# LED_Schematic.net
KiCad netlist of a schematic drawn in Altium Designer
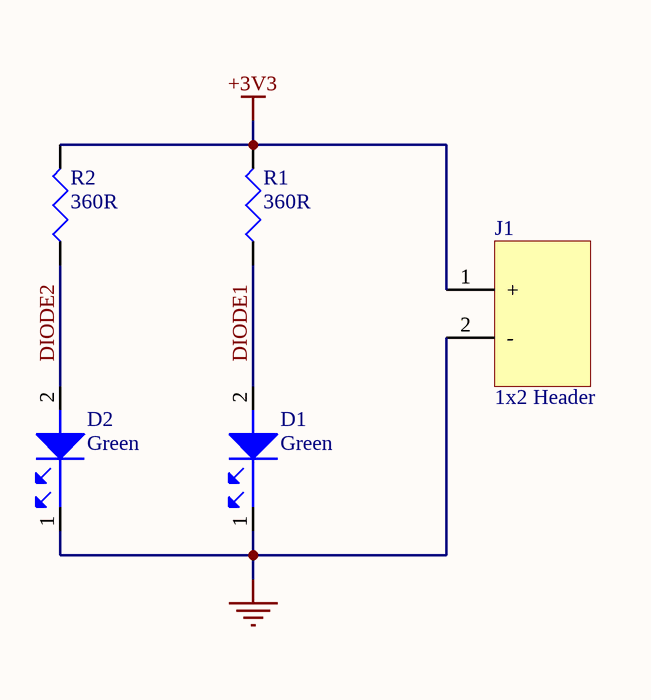
[diagram p0: LED Schematic.SchDoc]

(export (version "E")
  (design (tool "Eeschema 10.0.6"))
  (components
    (comp (ref "D1")
      (value "Green")
      (footprint "LED1540G")
      (description "Led Green/orange TSS-2 Type SMD")
      (fields
        (field (name "MANUFACTURER") "Panasonic")
        (field (name "MANUFACTURER PART NUMBER") "LNJ115W8ARA")
      )
      (libsource (lib "LED Schematic Library") (part "LNJ115W8ARA"))
    )
    (comp (ref "D2")
      (value "Green")
      (footprint "LED1540G")
      (description "Led Green/orange TSS-2 Type SMD")
      (fields
        (field (name "MANUFACTURER") "Panasonic")
        (field (name "MANUFACTURER PART NUMBER") "LNJ115W8ARA")
      )
      (libsource (lib "LED Schematic Library") (part "LNJ115W8ARA"))
    )
    (comp (ref "J1")
      (value "1x2 Header")
      (footprint "HDR1X2")
      (description "KK 254 Wire-to-Board Header, Vertical, with Friction Lock, 2 Circuits, Gold (Au) Plating")
      (fields (field (name "MANUFACTURER") "Molex") (field (name "MANUFACTURER PART NUMBER") "0022292021"))
      (libsource (lib "LED Schematic Library") (part "0022292021"))
    )
    (comp (ref "R1")
      (value "360R")
      (footprint "R0805")
      (description "SMD Chip Resistor, 360 Ohm, ± 1%, 125 mW, 0805 [2012 Metric], Thick Film, General Purpose")
      (fields
        (field (name "MANUFACTURER") "Vishay")
        (field (name "MANUFACTURER PART NUMBER") "CRCW0805360RFKEA")
      )
      (libsource (lib "LED Schematic Library") (part "CRCW0805360RFKEA"))
    )
    (comp (ref "R2")
      (value "360R")
      (footprint "R0805")
      (description "SMD Chip Resistor, 360 Ohm, ± 1%, 125 mW, 0805 [2012 Metric], Thick Film, General Purpose")
      (fields
        (field (name "MANUFACTURER") "Vishay")
        (field (name "MANUFACTURER PART NUMBER") "CRCW0805360RFKEA")
      )
      (libsource (lib "LED Schematic Library") (part "CRCW0805360RFKEA"))
    )
  )
  (nets
    (net (code "1") (name "+3V3") (class "Default")
      (node (ref "J1") (pin "1") (pinfunction "+_1") (pintype "passive"))
      (node (ref "R1") (pin "2") (pinfunction "2_2") (pintype "passive"))
      (node (ref "R2") (pin "2") (pinfunction "2_2") (pintype "passive"))
    )
    (net (code "2") (name "/DIODE1") (class "Default")
      (node (ref "D1") (pin "2") (pinfunction "2_2") (pintype "passive"))
      (node (ref "R1") (pin "1") (pinfunction "1_1") (pintype "passive"))
    )
    (net (code "3") (name "/DIODE2") (class "Default")
      (node (ref "D2") (pin "2") (pinfunction "2_2") (pintype "passive"))
      (node (ref "R2") (pin "1") (pinfunction "1_1") (pintype "passive"))
    )
    (net (code "4") (name "GND") (class "Default")
      (node (ref "D1") (pin "1") (pinfunction "1_1") (pintype "passive"))
      (node (ref "D2") (pin "1") (pinfunction "1_1") (pintype "passive"))
      (node (ref "J1") (pin "2") (pinfunction "-_2") (pintype "passive"))
    )
  )
)
